# DUAL_PROTECTED_INPUT.net
KiCad netlist of a schematic drawn in Altium Designer
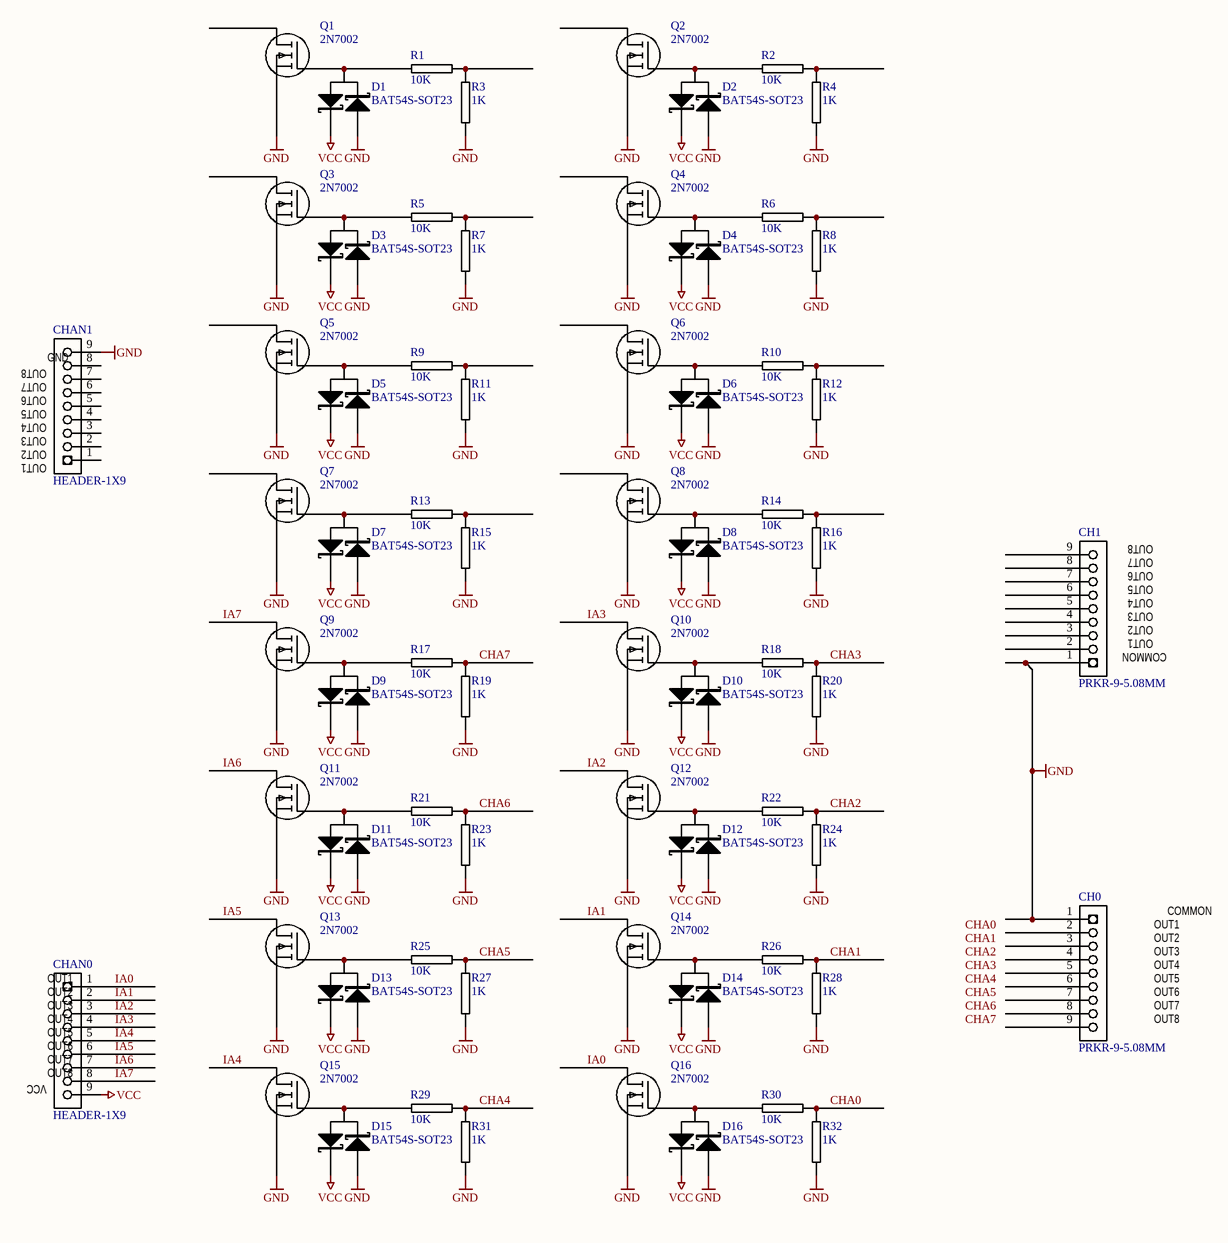
[diagram p0: DUAL PROTECTED INPUT.SchDoc]

(export (version "E")
  (design (tool "Eeschema 10.0.6"))
  (components
    (comp (ref "CH0")
      (value "PRKR-9-5.08MM")
      (footprint "PRKR-9-5.08MM")
      (libsource (lib "TH Connectors") (part "PRKR-9-5.08MM"))
    )
    (comp (ref "CH1")
      (value "PRKR-9-5.08MM")
      (footprint "PRKR-9-5.08MM")
      (libsource (lib "TH Connectors") (part "PRKR-9-5.08MM"))
    )
    (comp (ref "CHAN0")
      (value "HEADER-1X9")
      (footprint "HEADER-1X9")
      (libsource (lib "vh_Altium Library") (part "HEADER-1X9"))
    )
    (comp (ref "CHAN1")
      (value "HEADER-1X9")
      (footprint "HEADER-1X9")
      (libsource (lib "vh_Altium Library") (part "HEADER-1X9"))
    )
    (comp (ref "D1")
      (value "BAT54S-SOT23")
      (footprint "SOT23-123")
      (description "DUAL SCHOTTKY DIODE SERIES")
      (fields
        (field (name "MANUFACTURER PART NUMBER") "BAT54S,215")
        (field (name "MANUFACTURER") "NXP Semiconductors")
      )
      (libsource (lib "vh_Altium Library") (part "BAT54S-SOT23"))
    )
    (comp (ref "D2")
      (value "BAT54S-SOT23")
      (footprint "SOT23-123")
      (description "DUAL SCHOTTKY DIODE SERIES")
      (fields
        (field (name "MANUFACTURER PART NUMBER") "BAT54S,215")
        (field (name "MANUFACTURER") "NXP Semiconductors")
      )
      (libsource (lib "vh_Altium Library") (part "BAT54S-SOT23"))
    )
    (comp (ref "D3")
      (value "BAT54S-SOT23")
      (footprint "SOT23-123")
      (description "DUAL SCHOTTKY DIODE SERIES")
      (fields
        (field (name "MANUFACTURER PART NUMBER") "BAT54S,215")
        (field (name "MANUFACTURER") "NXP Semiconductors")
      )
      (libsource (lib "vh_Altium Library") (part "BAT54S-SOT23"))
    )
    (comp (ref "D4")
      (value "BAT54S-SOT23")
      (footprint "SOT23-123")
      (description "DUAL SCHOTTKY DIODE SERIES")
      (fields
        (field (name "MANUFACTURER PART NUMBER") "BAT54S,215")
        (field (name "MANUFACTURER") "NXP Semiconductors")
      )
      (libsource (lib "vh_Altium Library") (part "BAT54S-SOT23"))
    )
    (comp (ref "D5")
      (value "BAT54S-SOT23")
      (footprint "SOT23-123")
      (description "DUAL SCHOTTKY DIODE SERIES")
      (fields
        (field (name "MANUFACTURER PART NUMBER") "BAT54S,215")
        (field (name "MANUFACTURER") "NXP Semiconductors")
      )
      (libsource (lib "vh_Altium Library") (part "BAT54S-SOT23"))
    )
    (comp (ref "D6")
      (value "BAT54S-SOT23")
      (footprint "SOT23-123")
      (description "DUAL SCHOTTKY DIODE SERIES")
      (fields
        (field (name "MANUFACTURER PART NUMBER") "BAT54S,215")
        (field (name "MANUFACTURER") "NXP Semiconductors")
      )
      (libsource (lib "vh_Altium Library") (part "BAT54S-SOT23"))
    )
    (comp (ref "D7")
      (value "BAT54S-SOT23")
      (footprint "SOT23-123")
      (description "DUAL SCHOTTKY DIODE SERIES")
      (fields
        (field (name "MANUFACTURER PART NUMBER") "BAT54S,215")
        (field (name "MANUFACTURER") "NXP Semiconductors")
      )
      (libsource (lib "vh_Altium Library") (part "BAT54S-SOT23"))
    )
    (comp (ref "D8")
      (value "BAT54S-SOT23")
      (footprint "SOT23-123")
      (description "DUAL SCHOTTKY DIODE SERIES")
      (fields
        (field (name "MANUFACTURER PART NUMBER") "BAT54S,215")
        (field (name "MANUFACTURER") "NXP Semiconductors")
      )
      (libsource (lib "vh_Altium Library") (part "BAT54S-SOT23"))
    )
    (comp (ref "D9")
      (value "BAT54S-SOT23")
      (footprint "SOT23-123")
      (description "DUAL SCHOTTKY DIODE SERIES")
      (fields
        (field (name "MANUFACTURER PART NUMBER") "BAT54S,215")
        (field (name "MANUFACTURER") "NXP Semiconductors")
      )
      (libsource (lib "vh_Altium Library") (part "BAT54S-SOT23"))
    )
    (comp (ref "D10")
      (value "BAT54S-SOT23")
      (footprint "SOT23-123")
      (description "DUAL SCHOTTKY DIODE SERIES")
      (fields
        (field (name "MANUFACTURER PART NUMBER") "BAT54S,215")
        (field (name "MANUFACTURER") "NXP Semiconductors")
      )
      (libsource (lib "vh_Altium Library") (part "BAT54S-SOT23"))
    )
    (comp (ref "D11")
      (value "BAT54S-SOT23")
      (footprint "SOT23-123")
      (description "DUAL SCHOTTKY DIODE SERIES")
      (fields
        (field (name "MANUFACTURER PART NUMBER") "BAT54S,215")
        (field (name "MANUFACTURER") "NXP Semiconductors")
      )
      (libsource (lib "vh_Altium Library") (part "BAT54S-SOT23"))
    )
    (comp (ref "D12")
      (value "BAT54S-SOT23")
      (footprint "SOT23-123")
      (description "DUAL SCHOTTKY DIODE SERIES")
      (fields
        (field (name "MANUFACTURER PART NUMBER") "BAT54S,215")
        (field (name "MANUFACTURER") "NXP Semiconductors")
      )
      (libsource (lib "vh_Altium Library") (part "BAT54S-SOT23"))
    )
    (comp (ref "D13")
      (value "BAT54S-SOT23")
      (footprint "SOT23-123")
      (description "DUAL SCHOTTKY DIODE SERIES")
      (fields
        (field (name "MANUFACTURER PART NUMBER") "BAT54S,215")
        (field (name "MANUFACTURER") "NXP Semiconductors")
      )
      (libsource (lib "vh_Altium Library") (part "BAT54S-SOT23"))
    )
    (comp (ref "D14")
      (value "BAT54S-SOT23")
      (footprint "SOT23-123")
      (description "DUAL SCHOTTKY DIODE SERIES")
      (fields
        (field (name "MANUFACTURER PART NUMBER") "BAT54S,215")
        (field (name "MANUFACTURER") "NXP Semiconductors")
      )
      (libsource (lib "vh_Altium Library") (part "BAT54S-SOT23"))
    )
    (comp (ref "D15")
      (value "BAT54S-SOT23")
      (footprint "SOT23-123")
      (description "DUAL SCHOTTKY DIODE SERIES")
      (fields
        (field (name "MANUFACTURER PART NUMBER") "BAT54S,215")
        (field (name "MANUFACTURER") "NXP Semiconductors")
      )
      (libsource (lib "vh_Altium Library") (part "BAT54S-SOT23"))
    )
    (comp (ref "D16")
      (value "BAT54S-SOT23")
      (footprint "SOT23-123")
      (description "DUAL SCHOTTKY DIODE SERIES")
      (fields
        (field (name "MANUFACTURER PART NUMBER") "BAT54S,215")
        (field (name "MANUFACTURER") "NXP Semiconductors")
      )
      (libsource (lib "vh_Altium Library") (part "BAT54S-SOT23"))
    )
    (comp (ref "Q1")
      (value "2N7002")
      (footprint "SOT23-GDS")
      (description "MOSFET N-CH 60V 115MA SOT-23")
      (fields (field (name "MANUFACTURER") "Fairchild Semiconductor"))
      (libsource (lib "vh_Altium Library") (part "2N7002-SOT23"))
    )
    (comp (ref "Q2")
      (value "2N7002")
      (footprint "SOT23-GDS")
      (description "MOSFET N-CH 60V 115MA SOT-23")
      (fields (field (name "MANUFACTURER") "Fairchild Semiconductor"))
      (libsource (lib "vh_Altium Library") (part "2N7002-SOT23"))
    )
    (comp (ref "Q3")
      (value "2N7002")
      (footprint "SOT23-GDS")
      (description "MOSFET N-CH 60V 115MA SOT-23")
      (fields (field (name "MANUFACTURER") "Fairchild Semiconductor"))
      (libsource (lib "vh_Altium Library") (part "2N7002-SOT23"))
    )
    (comp (ref "Q4")
      (value "2N7002")
      (footprint "SOT23-GDS")
      (description "MOSFET N-CH 60V 115MA SOT-23")
      (fields (field (name "MANUFACTURER") "Fairchild Semiconductor"))
      (libsource (lib "vh_Altium Library") (part "2N7002-SOT23"))
    )
    (comp (ref "Q5")
      (value "2N7002")
      (footprint "SOT23-GDS")
      (description "MOSFET N-CH 60V 115MA SOT-23")
      (fields (field (name "MANUFACTURER") "Fairchild Semiconductor"))
      (libsource (lib "vh_Altium Library") (part "2N7002-SOT23"))
    )
    (comp (ref "Q6")
      (value "2N7002")
      (footprint "SOT23-GDS")
      (description "MOSFET N-CH 60V 115MA SOT-23")
      (fields (field (name "MANUFACTURER") "Fairchild Semiconductor"))
      (libsource (lib "vh_Altium Library") (part "2N7002-SOT23"))
    )
    (comp (ref "Q7")
      (value "2N7002")
      (footprint "SOT23-GDS")
      (description "MOSFET N-CH 60V 115MA SOT-23")
      (fields (field (name "MANUFACTURER") "Fairchild Semiconductor"))
      (libsource (lib "vh_Altium Library") (part "2N7002-SOT23"))
    )
    (comp (ref "Q8")
      (value "2N7002")
      (footprint "SOT23-GDS")
      (description "MOSFET N-CH 60V 115MA SOT-23")
      (fields (field (name "MANUFACTURER") "Fairchild Semiconductor"))
      (libsource (lib "vh_Altium Library") (part "2N7002-SOT23"))
    )
    (comp (ref "Q9")
      (value "2N7002")
      (footprint "SOT23-GDS")
      (description "MOSFET N-CH 60V 115MA SOT-23")
      (fields (field (name "MANUFACTURER") "Fairchild Semiconductor"))
      (libsource (lib "vh_Altium Library") (part "2N7002-SOT23"))
    )
    (comp (ref "Q10")
      (value "2N7002")
      (footprint "SOT23-GDS")
      (description "MOSFET N-CH 60V 115MA SOT-23")
      (fields (field (name "MANUFACTURER") "Fairchild Semiconductor"))
      (libsource (lib "vh_Altium Library") (part "2N7002-SOT23"))
    )
    (comp (ref "Q11")
      (value "2N7002")
      (footprint "SOT23-GDS")
      (description "MOSFET N-CH 60V 115MA SOT-23")
      (fields (field (name "MANUFACTURER") "Fairchild Semiconductor"))
      (libsource (lib "vh_Altium Library") (part "2N7002-SOT23"))
    )
    (comp (ref "Q12")
      (value "2N7002")
      (footprint "SOT23-GDS")
      (description "MOSFET N-CH 60V 115MA SOT-23")
      (fields (field (name "MANUFACTURER") "Fairchild Semiconductor"))
      (libsource (lib "vh_Altium Library") (part "2N7002-SOT23"))
    )
    (comp (ref "Q13")
      (value "2N7002")
      (footprint "SOT23-GDS")
      (description "MOSFET N-CH 60V 115MA SOT-23")
      (fields (field (name "MANUFACTURER") "Fairchild Semiconductor"))
      (libsource (lib "vh_Altium Library") (part "2N7002-SOT23"))
    )
    (comp (ref "Q14")
      (value "2N7002")
      (footprint "SOT23-GDS")
      (description "MOSFET N-CH 60V 115MA SOT-23")
      (fields (field (name "MANUFACTURER") "Fairchild Semiconductor"))
      (libsource (lib "vh_Altium Library") (part "2N7002-SOT23"))
    )
    (comp (ref "Q15")
      (value "2N7002")
      (footprint "SOT23-GDS")
      (description "MOSFET N-CH 60V 115MA SOT-23")
      (fields (field (name "MANUFACTURER") "Fairchild Semiconductor"))
      (libsource (lib "vh_Altium Library") (part "2N7002-SOT23"))
    )
    (comp (ref "Q16")
      (value "2N7002")
      (footprint "SOT23-GDS")
      (description "MOSFET N-CH 60V 115MA SOT-23")
      (fields (field (name "MANUFACTURER") "Fairchild Semiconductor"))
      (libsource (lib "vh_Altium Library") (part "2N7002-SOT23"))
    )
    (comp (ref "R1")
      (value "10K")
      (footprint "0805R-10K")
      (description "RESISTOR 0805 1/4 WATT THIN FILM")
      (libsource (lib "vh_Altium Library") (part "0805R-10K"))
    )
    (comp (ref "R2")
      (value "10K")
      (footprint "0805R-10K")
      (description "RESISTOR 0805 1/4 WATT THIN FILM")
      (libsource (lib "vh_Altium Library") (part "0805R-10K"))
    )
    (comp (ref "R3")
      (value "1K")
      (footprint "0805R-1K")
      (description "RESISTOR 0805 1/4 WATT THIN FILM")
      (libsource (lib "vh_Altium Library") (part "0805R-1K"))
    )
    (comp (ref "R4")
      (value "1K")
      (footprint "0805R-1K")
      (description "RESISTOR 0805 1/4 WATT THIN FILM")
      (libsource (lib "vh_Altium Library") (part "0805R-1K"))
    )
    (comp (ref "R5")
      (value "10K")
      (footprint "0805R-10K")
      (description "RESISTOR 0805 1/4 WATT THIN FILM")
      (libsource (lib "vh_Altium Library") (part "0805R-10K"))
    )
    (comp (ref "R6")
      (value "10K")
      (footprint "0805R-10K")
      (description "RESISTOR 0805 1/4 WATT THIN FILM")
      (libsource (lib "vh_Altium Library") (part "0805R-10K"))
    )
    (comp (ref "R7")
      (value "1K")
      (footprint "0805R-1K")
      (description "RESISTOR 0805 1/4 WATT THIN FILM")
      (libsource (lib "vh_Altium Library") (part "0805R-1K"))
    )
    (comp (ref "R8")
      (value "1K")
      (footprint "0805R-1K")
      (description "RESISTOR 0805 1/4 WATT THIN FILM")
      (libsource (lib "vh_Altium Library") (part "0805R-1K"))
    )
    (comp (ref "R9")
      (value "10K")
      (footprint "0805R-10K")
      (description "RESISTOR 0805 1/4 WATT THIN FILM")
      (libsource (lib "vh_Altium Library") (part "0805R-10K"))
    )
    (comp (ref "R10")
      (value "10K")
      (footprint "0805R-10K")
      (description "RESISTOR 0805 1/4 WATT THIN FILM")
      (libsource (lib "vh_Altium Library") (part "0805R-10K"))
    )
    (comp (ref "R11")
      (value "1K")
      (footprint "0805R-1K")
      (description "RESISTOR 0805 1/4 WATT THIN FILM")
      (libsource (lib "vh_Altium Library") (part "0805R-1K"))
    )
    (comp (ref "R12")
      (value "1K")
      (footprint "0805R-1K")
      (description "RESISTOR 0805 1/4 WATT THIN FILM")
      (libsource (lib "vh_Altium Library") (part "0805R-1K"))
    )
    (comp (ref "R13")
      (value "10K")
      (footprint "0805R-10K")
      (description "RESISTOR 0805 1/4 WATT THIN FILM")
      (libsource (lib "vh_Altium Library") (part "0805R-10K"))
    )
    (comp (ref "R14")
      (value "10K")
      (footprint "0805R-10K")
      (description "RESISTOR 0805 1/4 WATT THIN FILM")
      (libsource (lib "vh_Altium Library") (part "0805R-10K"))
    )
    (comp (ref "R15")
      (value "1K")
      (footprint "0805R-1K")
      (description "RESISTOR 0805 1/4 WATT THIN FILM")
      (libsource (lib "vh_Altium Library") (part "0805R-1K"))
    )
    (comp (ref "R16")
      (value "1K")
      (footprint "0805R-1K")
      (description "RESISTOR 0805 1/4 WATT THIN FILM")
      (libsource (lib "vh_Altium Library") (part "0805R-1K"))
    )
    (comp (ref "R17")
      (value "10K")
      (footprint "0805R-10K")
      (description "RESISTOR 0805 1/4 WATT THIN FILM")
      (libsource (lib "vh_Altium Library") (part "0805R-10K"))
    )
    (comp (ref "R18")
      (value "10K")
      (footprint "0805R-10K")
      (description "RESISTOR 0805 1/4 WATT THIN FILM")
      (libsource (lib "vh_Altium Library") (part "0805R-10K"))
    )
    (comp (ref "R19")
      (value "1K")
      (footprint "0805R-1K")
      (description "RESISTOR 0805 1/4 WATT THIN FILM")
      (libsource (lib "vh_Altium Library") (part "0805R-1K"))
    )
    (comp (ref "R20")
      (value "1K")
      (footprint "0805R-1K")
      (description "RESISTOR 0805 1/4 WATT THIN FILM")
      (libsource (lib "vh_Altium Library") (part "0805R-1K"))
    )
    (comp (ref "R21")
      (value "10K")
      (footprint "0805R-10K")
      (description "RESISTOR 0805 1/4 WATT THIN FILM")
      (libsource (lib "vh_Altium Library") (part "0805R-10K"))
    )
    (comp (ref "R22")
      (value "10K")
      (footprint "0805R-10K")
      (description "RESISTOR 0805 1/4 WATT THIN FILM")
      (libsource (lib "vh_Altium Library") (part "0805R-10K"))
    )
    (comp (ref "R23")
      (value "1K")
      (footprint "0805R-1K")
      (description "RESISTOR 0805 1/4 WATT THIN FILM")
      (libsource (lib "vh_Altium Library") (part "0805R-1K"))
    )
    (comp (ref "R24")
      (value "1K")
      (footprint "0805R-1K")
      (description "RESISTOR 0805 1/4 WATT THIN FILM")
      (libsource (lib "vh_Altium Library") (part "0805R-1K"))
    )
    (comp (ref "R25")
      (value "10K")
      (footprint "0805R-10K")
      (description "RESISTOR 0805 1/4 WATT THIN FILM")
      (libsource (lib "vh_Altium Library") (part "0805R-10K"))
    )
    (comp (ref "R26")
      (value "10K")
      (footprint "0805R-10K")
      (description "RESISTOR 0805 1/4 WATT THIN FILM")
      (libsource (lib "vh_Altium Library") (part "0805R-10K"))
    )
    (comp (ref "R27")
      (value "1K")
      (footprint "0805R-1K")
      (description "RESISTOR 0805 1/4 WATT THIN FILM")
      (libsource (lib "vh_Altium Library") (part "0805R-1K"))
    )
    (comp (ref "R28")
      (value "1K")
      (footprint "0805R-1K")
      (description "RESISTOR 0805 1/4 WATT THIN FILM")
      (libsource (lib "vh_Altium Library") (part "0805R-1K"))
    )
    (comp (ref "R29")
      (value "10K")
      (footprint "0805R-10K")
      (description "RESISTOR 0805 1/4 WATT THIN FILM")
      (libsource (lib "vh_Altium Library") (part "0805R-10K"))
    )
    (comp (ref "R30")
      (value "10K")
      (footprint "0805R-10K")
      (description "RESISTOR 0805 1/4 WATT THIN FILM")
      (libsource (lib "vh_Altium Library") (part "0805R-10K"))
    )
    (comp (ref "R31")
      (value "1K")
      (footprint "0805R-1K")
      (description "RESISTOR 0805 1/4 WATT THIN FILM")
      (libsource (lib "vh_Altium Library") (part "0805R-1K"))
    )
    (comp (ref "R32")
      (value "1K")
      (footprint "0805R-1K")
      (description "RESISTOR 0805 1/4 WATT THIN FILM")
      (libsource (lib "vh_Altium Library") (part "0805R-1K"))
    )
  )
  (nets
    (net (code "1") (name "/CHA0") (class "Default")
      (node (ref "R30") (pin "2") (pintype "passive"))
      (node (ref "R32") (pin "1") (pintype "passive"))
    )
    (net (code "2") (name "/CHA1") (class "Default")
      (node (ref "R26") (pin "2") (pintype "passive"))
      (node (ref "R28") (pin "1") (pintype "passive"))
    )
    (net (code "3") (name "/CHA2") (class "Default")
      (node (ref "R22") (pin "2") (pintype "passive"))
      (node (ref "R24") (pin "1") (pintype "passive"))
    )
    (net (code "4") (name "/CHA3") (class "Default")
      (node (ref "R18") (pin "2") (pintype "passive"))
      (node (ref "R20") (pin "1") (pintype "passive"))
    )
    (net (code "5") (name "/CHA4") (class "Default")
      (node (ref "R29") (pin "2") (pintype "passive"))
      (node (ref "R31") (pin "1") (pintype "passive"))
    )
    (net (code "6") (name "/CHA5") (class "Default")
      (node (ref "R25") (pin "2") (pintype "passive"))
      (node (ref "R27") (pin "1") (pintype "passive"))
    )
    (net (code "7") (name "/CHA6") (class "Default")
      (node (ref "R21") (pin "2") (pintype "passive"))
      (node (ref "R23") (pin "1") (pintype "passive"))
    )
    (net (code "8") (name "/CHA7") (class "Default")
      (node (ref "R17") (pin "2") (pintype "passive"))
      (node (ref "R19") (pin "1") (pintype "passive"))
    )
    (net (code "9") (name "/IA0") (class "Default")
      (node (ref "CHAN0") (pin "1") (pintype "passive"))
      (node (ref "Q16") (pin "D") (pintype "passive"))
    )
    (net (code "10") (name "/IA1") (class "Default")
      (node (ref "CHAN0") (pin "2") (pintype "passive"))
      (node (ref "Q14") (pin "D") (pintype "passive"))
    )
    (net (code "11") (name "/IA2") (class "Default")
      (node (ref "CHAN0") (pin "3") (pintype "passive"))
      (node (ref "Q12") (pin "D") (pintype "passive"))
    )
    (net (code "12") (name "/IA3") (class "Default")
      (node (ref "CHAN0") (pin "4") (pintype "passive"))
      (node (ref "Q10") (pin "D") (pintype "passive"))
    )
    (net (code "13") (name "/IA4") (class "Default")
      (node (ref "CHAN0") (pin "5") (pintype "passive"))
      (node (ref "Q15") (pin "D") (pintype "passive"))
    )
    (net (code "14") (name "/IA5") (class "Default")
      (node (ref "CHAN0") (pin "6") (pintype "passive"))
      (node (ref "Q13") (pin "D") (pintype "passive"))
    )
    (net (code "15") (name "/IA6") (class "Default")
      (node (ref "CHAN0") (pin "7") (pintype "passive"))
      (node (ref "Q11") (pin "D") (pintype "passive"))
    )
    (net (code "16") (name "/IA7") (class "Default")
      (node (ref "CHAN0") (pin "8") (pintype "passive"))
      (node (ref "Q9") (pin "D") (pintype "passive"))
    )
    (net (code "17") (name "GND") (class "Default")
      (node (ref "CH0") (pin "1") (pintype "passive"))
      (node (ref "CH1") (pin "1") (pintype "passive"))
      (node (ref "CHAN1") (pin "9") (pintype "passive"))
      (node (ref "D1") (pin "1") (pinfunction "1_1") (pintype "passive"))
      (node (ref "D10") (pin "1") (pinfunction "1_1") (pintype "passive"))
      (node (ref "D11") (pin "1") (pinfunction "1_1") (pintype "passive"))
      (node (ref "D12") (pin "1") (pinfunction "1_1") (pintype "passive"))
      (node (ref "D13") (pin "1") (pinfunction "1_1") (pintype "passive"))
      (node (ref "D14") (pin "1") (pinfunction "1_1") (pintype "passive"))
      (node (ref "D15") (pin "1") (pinfunction "1_1") (pintype "passive"))
      (node (ref "D16") (pin "1") (pinfunction "1_1") (pintype "passive"))
      (node (ref "D2") (pin "1") (pinfunction "1_1") (pintype "passive"))
      (node (ref "D3") (pin "1") (pinfunction "1_1") (pintype "passive"))
      (node (ref "D4") (pin "1") (pinfunction "1_1") (pintype "passive"))
      (node (ref "D5") (pin "1") (pinfunction "1_1") (pintype "passive"))
      (node (ref "D6") (pin "1") (pinfunction "1_1") (pintype "passive"))
      (node (ref "D7") (pin "1") (pinfunction "1_1") (pintype "passive"))
      (node (ref "D8") (pin "1") (pinfunction "1_1") (pintype "passive"))
      (node (ref "D9") (pin "1") (pinfunction "1_1") (pintype "passive"))
      (node (ref "Q1") (pin "S") (pintype "passive"))
      (node (ref "Q10") (pin "S") (pintype "passive"))
      (node (ref "Q11") (pin "S") (pintype "passive"))
      (node (ref "Q12") (pin "S") (pintype "passive"))
      (node (ref "Q13") (pin "S") (pintype "passive"))
      (node (ref "Q14") (pin "S") (pintype "passive"))
      (node (ref "Q15") (pin "S") (pintype "passive"))
      (node (ref "Q16") (pin "S") (pintype "passive"))
      (node (ref "Q2") (pin "S") (pintype "passive"))
      (node (ref "Q3") (pin "S") (pintype "passive"))
      (node (ref "Q4") (pin "S") (pintype "passive"))
      (node (ref "Q5") (pin "S") (pintype "passive"))
      (node (ref "Q6") (pin "S") (pintype "passive"))
      (node (ref "Q7") (pin "S") (pintype "passive"))
      (node (ref "Q8") (pin "S") (pintype "passive"))
      (node (ref "Q9") (pin "S") (pintype "passive"))
      (node (ref "R11") (pin "2") (pintype "passive"))
      (node (ref "R12") (pin "2") (pintype "passive"))
      (node (ref "R15") (pin "2") (pintype "passive"))
      (node (ref "R16") (pin "2") (pintype "passive"))
      (node (ref "R19") (pin "2") (pintype "passive"))
      (node (ref "R20") (pin "2") (pintype "passive"))
      (node (ref "R23") (pin "2") (pintype "passive"))
      (node (ref "R24") (pin "2") (pintype "passive"))
      (node (ref "R27") (pin "2") (pintype "passive"))
      (node (ref "R28") (pin "2") (pintype "passive"))
      (node (ref "R3") (pin "2") (pintype "passive"))
      (node (ref "R31") (pin "2") (pintype "passive"))
      (node (ref "R32") (pin "2") (pintype "passive"))
      (node (ref "R4") (pin "2") (pintype "passive"))
      (node (ref "R7") (pin "2") (pintype "passive"))
      (node (ref "R8") (pin "2") (pintype "passive"))
    )
    (net (code "18") (name "Net-(D1-Pad3)") (class "Default")
      (node (ref "D1") (pin "3") (pinfunction "3_3") (pintype "passive"))
      (node (ref "Q1") (pin "G") (pintype "passive"))
      (node (ref "R1") (pin "1") (pintype "passive"))
    )
    (net (code "19") (name "Net-(D2-Pad3)") (class "Default")
      (node (ref "D2") (pin "3") (pinfunction "3_3") (pintype "passive"))
      (node (ref "Q2") (pin "G") (pintype "passive"))
      (node (ref "R2") (pin "1") (pintype "passive"))
    )
    (net (code "20") (name "Net-(D3-Pad3)") (class "Default")
      (node (ref "D3") (pin "3") (pinfunction "3_3") (pintype "passive"))
      (node (ref "Q3") (pin "G") (pintype "passive"))
      (node (ref "R5") (pin "1") (pintype "passive"))
    )
    (net (code "21") (name "Net-(D4-Pad3)") (class "Default")
      (node (ref "D4") (pin "3") (pinfunction "3_3") (pintype "passive"))
      (node (ref "Q4") (pin "G") (pintype "passive"))
      (node (ref "R6") (pin "1") (pintype "passive"))
    )
    (net (code "22") (name "Net-(D5-Pad3)") (class "Default")
      (node (ref "D5") (pin "3") (pinfunction "3_3") (pintype "passive"))
      (node (ref "Q5") (pin "G") (pintype "passive"))
      (node (ref "R9") (pin "1") (pintype "passive"))
    )
    (net (code "23") (name "Net-(D6-Pad3)") (class "Default")
      (node (ref "D6") (pin "3") (pinfunction "3_3") (pintype "passive"))
      (node (ref "Q6") (pin "G") (pintype "passive"))
      (node (ref "R10") (pin "1") (pintype "passive"))
    )
    (net (code "24") (name "Net-(D7-Pad3)") (class "Default")
      (node (ref "D7") (pin "3") (pinfunction "3_3") (pintype "passive"))
      (node (ref "Q7") (pin "G") (pintype "passive"))
      (node (ref "R13") (pin "1") (pintype "passive"))
    )
    (net (code "25") (name "Net-(D8-Pad3)") (class "Default")
      (node (ref "D8") (pin "3") (pinfunction "3_3") (pintype "passive"))
      (node (ref "Q8") (pin "G") (pintype "passive"))
      (node (ref "R14") (pin "1") (pintype "passive"))
    )
    (net (code "26") (name "Net-(D9-Pad3)") (class "Default")
      (node (ref "D9") (pin "3") (pinfunction "3_3") (pintype "passive"))
      (node (ref "Q9") (pin "G") (pintype "passive"))
      (node (ref "R17") (pin "1") (pintype "passive"))
    )
    (net (code "27") (name "Net-(D10-Pad3)") (class "Default")
      (node (ref "D10") (pin "3") (pinfunction "3_3") (pintype "passive"))
      (node (ref "Q10") (pin "G") (pintype "passive"))
      (node (ref "R18") (pin "1") (pintype "passive"))
    )
    (net (code "28") (name "Net-(D11-Pad3)") (class "Default")
      (node (ref "D11") (pin "3") (pinfunction "3_3") (pintype "passive"))
      (node (ref "Q11") (pin "G") (pintype "passive"))
      (node (ref "R21") (pin "1") (pintype "passive"))
    )
    (net (code "29") (name "Net-(D12-Pad3)") (class "Default")
      (node (ref "D12") (pin "3") (pinfunction "3_3") (pintype "passive"))
      (node (ref "Q12") (pin "G") (pintype "passive"))
      (node (ref "R22") (pin "1") (pintype "passive"))
    )
    (net (code "30") (name "Net-(D13-Pad3)") (class "Default")
      (node (ref "D13") (pin "3") (pinfunction "3_3") (pintype "passive"))
      (node (ref "Q13") (pin "G") (pintype "passive"))
      (node (ref "R25") (pin "1") (pintype "passive"))
    )
    (net (code "31") (name "Net-(D14-Pad3)") (class "Default")
      (node (ref "D14") (pin "3") (pinfunction "3_3") (pintype "passive"))
      (node (ref "Q14") (pin "G") (pintype "passive"))
      (node (ref "R26") (pin "1") (pintype "passive"))
    )
    (net (code "32") (name "Net-(D15-Pad3)") (class "Default")
      (node (ref "D15") (pin "3") (pinfunction "3_3") (pintype "passive"))
      (node (ref "Q15") (pin "G") (pintype "passive"))
      (node (ref "R29") (pin "1") (pintype "passive"))
    )
    (net (code "33") (name "Net-(D16-Pad3)") (class "Default")
      (node (ref "D16") (pin "3") (pinfunction "3_3") (pintype "passive"))
      (node (ref "Q16") (pin "G") (pintype "passive"))
      (node (ref "R30") (pin "1") (pintype "passive"))
    )
    (net (code "34") (name "Net-(R1-Pad2)") (class "Default")
      (node (ref "R1") (pin "2") (pintype "passive"))
      (node (ref "R3") (pin "1") (pintype "passive"))
    )
    (net (code "35") (name "Net-(R2-Pad2)") (class "Default")
      (node (ref "R2") (pin "2") (pintype "passive"))
      (node (ref "R4") (pin "1") (pintype "passive"))
    )
    (net (code "36") (name "Net-(R5-Pad2)") (class "Default")
      (node (ref "R5") (pin "2") (pintype "passive"))
      (node (ref "R7") (pin "1") (pintype "passive"))
    )
    (net (code "37") (name "Net-(R6-Pad2)") (class "Default")
      (node (ref "R6") (pin "2") (pintype "passive"))
      (node (ref "R8") (pin "1") (pintype "passive"))
    )
    (net (code "38") (name "Net-(R10-Pad2)") (class "Default")
      (node (ref "R10") (pin "2") (pintype "passive"))
      (node (ref "R12") (pin "1") (pintype "passive"))
    )
    (net (code "39") (name "Net-(R11-Pad1)") (class "Default")
      (node (ref "R11") (pin "1") (pintype "passive"))
      (node (ref "R9") (pin "2") (pintype "passive"))
    )
    (net (code "40") (name "Net-(R13-Pad2)") (class "Default")
      (node (ref "R13") (pin "2") (pintype "passive"))
      (node (ref "R15") (pin "1") (pintype "passive"))
    )
    (net (code "41") (name "Net-(R14-Pad2)") (class "Default")
      (node (ref "R14") (pin "2") (pintype "passive"))
      (node (ref "R16") (pin "1") (pintype "passive"))
    )
    (net (code "42") (name "VCC") (class "Default")
      (node (ref "CHAN0") (pin "9") (pintype "passive"))
      (node (ref "D1") (pin "2") (pinfunction "2_2") (pintype "passive"))
      (node (ref "D10") (pin "2") (pinfunction "2_2") (pintype "passive"))
      (node (ref "D11") (pin "2") (pinfunction "2_2") (pintype "passive"))
      (node (ref "D12") (pin "2") (pinfunction "2_2") (pintype "passive"))
      (node (ref "D13") (pin "2") (pinfunction "2_2") (pintype "passive"))
      (node (ref "D14") (pin "2") (pinfunction "2_2") (pintype "passive"))
      (node (ref "D15") (pin "2") (pinfunction "2_2") (pintype "passive"))
      (node (ref "D16") (pin "2") (pinfunction "2_2") (pintype "passive"))
      (node (ref "D2") (pin "2") (pinfunction "2_2") (pintype "passive"))
      (node (ref "D3") (pin "2") (pinfunction "2_2") (pintype "passive"))
      (node (ref "D4") (pin "2") (pinfunction "2_2") (pintype "passive"))
      (node (ref "D5") (pin "2") (pinfunction "2_2") (pintype "passive"))
      (node (ref "D6") (pin "2") (pinfunction "2_2") (pintype "passive"))
      (node (ref "D7") (pin "2") (pinfunction "2_2") (pintype "passive"))
      (node (ref "D8") (pin "2") (pinfunction "2_2") (pintype "passive"))
      (node (ref "D9") (pin "2") (pinfunction "2_2") (pintype "passive"))
    )
    (net (code "43") (name "unconnected-(CH0-Pad2)") (class "Default")
      (node (ref "CH0") (pin "2") (pintype "passive"))
    )
    (net (code "44") (name "unconnected-(CH0-Pad3)") (class "Default")
      (node (ref "CH0") (pin "3") (pintype "passive"))
    )
    (net (code "45") (name "unconnected-(CH0-Pad4)") (class "Default")
      (node (ref "CH0") (pin "4") (pintype "passive"))
    )
    (net (code "46") (name "unconnected-(CH0-Pad5)") (class "Default")
      (node (ref "CH0") (pin "5") (pintype "passive"))
    )
    (net (code "47") (name "unconnected-(CH0-Pad6)") (class "Default")
      (node (ref "CH0") (pin "6") (pintype "passive"))
    )
    (net (code "48") (name "unconnected-(CH0-Pad7)") (class "Default")
      (node (ref "CH0") (pin "7") (pintype "passive"))
    )
    (net (code "49") (name "unconnected-(CH0-Pad8)") (class "Default")
      (node (ref "CH0") (pin "8") (pintype "passive"))
    )
    (net (code "50") (name "unconnected-(CH0-Pad9)") (class "Default")
      (node (ref "CH0") (pin "9") (pintype "passive"))
    )
    (net (code "51") (name "unconnected-(CH1-Pad2)") (class "Default")
      (node (ref "CH1") (pin "2") (pintype "passive"))
    )
    (net (code "52") (name "unconnected-(CH1-Pad3)") (class "Default")
      (node (ref "CH1") (pin "3") (pintype "passive"))
    )
    (net (code "53") (name "unconnected-(CH1-Pad4)") (class "Default")
      (node (ref "CH1") (pin "4") (pintype "passive"))
    )
    (net (code "54") (name "unconnected-(CH1-Pad5)") (class "Default")
      (node (ref "CH1") (pin "5") (pintype "passive"))
    )
    (net (code "55") (name "unconnected-(CH1-Pad6)") (class "Default")
      (node (ref "CH1") (pin "6") (pintype "passive"))
    )
    (net (code "56") (name "unconnected-(CH1-Pad7)") (class "Default")
      (node (ref "CH1") (pin "7") (pintype "passive"))
    )
    (net (code "57") (name "unconnected-(CH1-Pad8)") (class "Default")
      (node (ref "CH1") (pin "8") (pintype "passive"))
    )
    (net (code "58") (name "unconnected-(CH1-Pad9)") (class "Default")
      (node (ref "CH1") (pin "9") (pintype "passive"))
    )
    (net (code "59") (name "unconnected-(CHAN1-Pad1)") (class "Default")
      (node (ref "CHAN1") (pin "1") (pintype "passive"))
    )
    (net (code "60") (name "unconnected-(CHAN1-Pad2)") (class "Default")
      (node (ref "CHAN1") (pin "2") (pintype "passive"))
    )
    (net (code "61") (name "unconnected-(CHAN1-Pad3)") (class "Default")
      (node (ref "CHAN1") (pin "3") (pintype "passive"))
    )
    (net (code "62") (name "unconnected-(CHAN1-Pad4)") (class "Default")
      (node (ref "CHAN1") (pin "4") (pintype "passive"))
    )
    (net (code "63") (name "unconnected-(CHAN1-Pad5)") (class "Default")
      (node (ref "CHAN1") (pin "5") (pintype "passive"))
    )
    (net (code "64") (name "unconnected-(CHAN1-Pad6)") (class "Default")
      (node (ref "CHAN1") (pin "6") (pintype "passive"))
    )
    (net (code "65") (name "unconnected-(CHAN1-Pad7)") (class "Default")
      (node (ref "CHAN1") (pin "7") (pintype "passive"))
    )
    (net (code "66") (name "unconnected-(CHAN1-Pad8)") (class "Default")
      (node (ref "CHAN1") (pin "8") (pintype "passive"))
    )
    (net (code "67") (name "unconnected-(Q1-PadD)") (class "Default")
      (node (ref "Q1") (pin "D") (pintype "passive"))
    )
    (net (code "68") (name "unconnected-(Q2-PadD)") (class "Default")
      (node (ref "Q2") (pin "D") (pintype "passive"))
    )
    (net (code "69") (name "unconnected-(Q3-PadD)") (class "Default")
      (node (ref "Q3") (pin "D") (pintype "passive"))
    )
    (net (code "70") (name "unconnected-(Q4-PadD)") (class "Default")
      (node (ref "Q4") (pin "D") (pintype "passive"))
    )
    (net (code "71") (name "unconnected-(Q5-PadD)") (class "Default")
      (node (ref "Q5") (pin "D") (pintype "passive"))
    )
    (net (code "72") (name "unconnected-(Q6-PadD)") (class "Default")
      (node (ref "Q6") (pin "D") (pintype "passive"))
    )
    (net (code "73") (name "unconnected-(Q7-PadD)") (class "Default")
      (node (ref "Q7") (pin "D") (pintype "passive"))
    )
    (net (code "74") (name "unconnected-(Q8-PadD)") (class "Default")
      (node (ref "Q8") (pin "D") (pintype "passive"))
    )
  )
)
